# mulato-32m.net
KiCad netlist of a schematic drawn in EAGLE
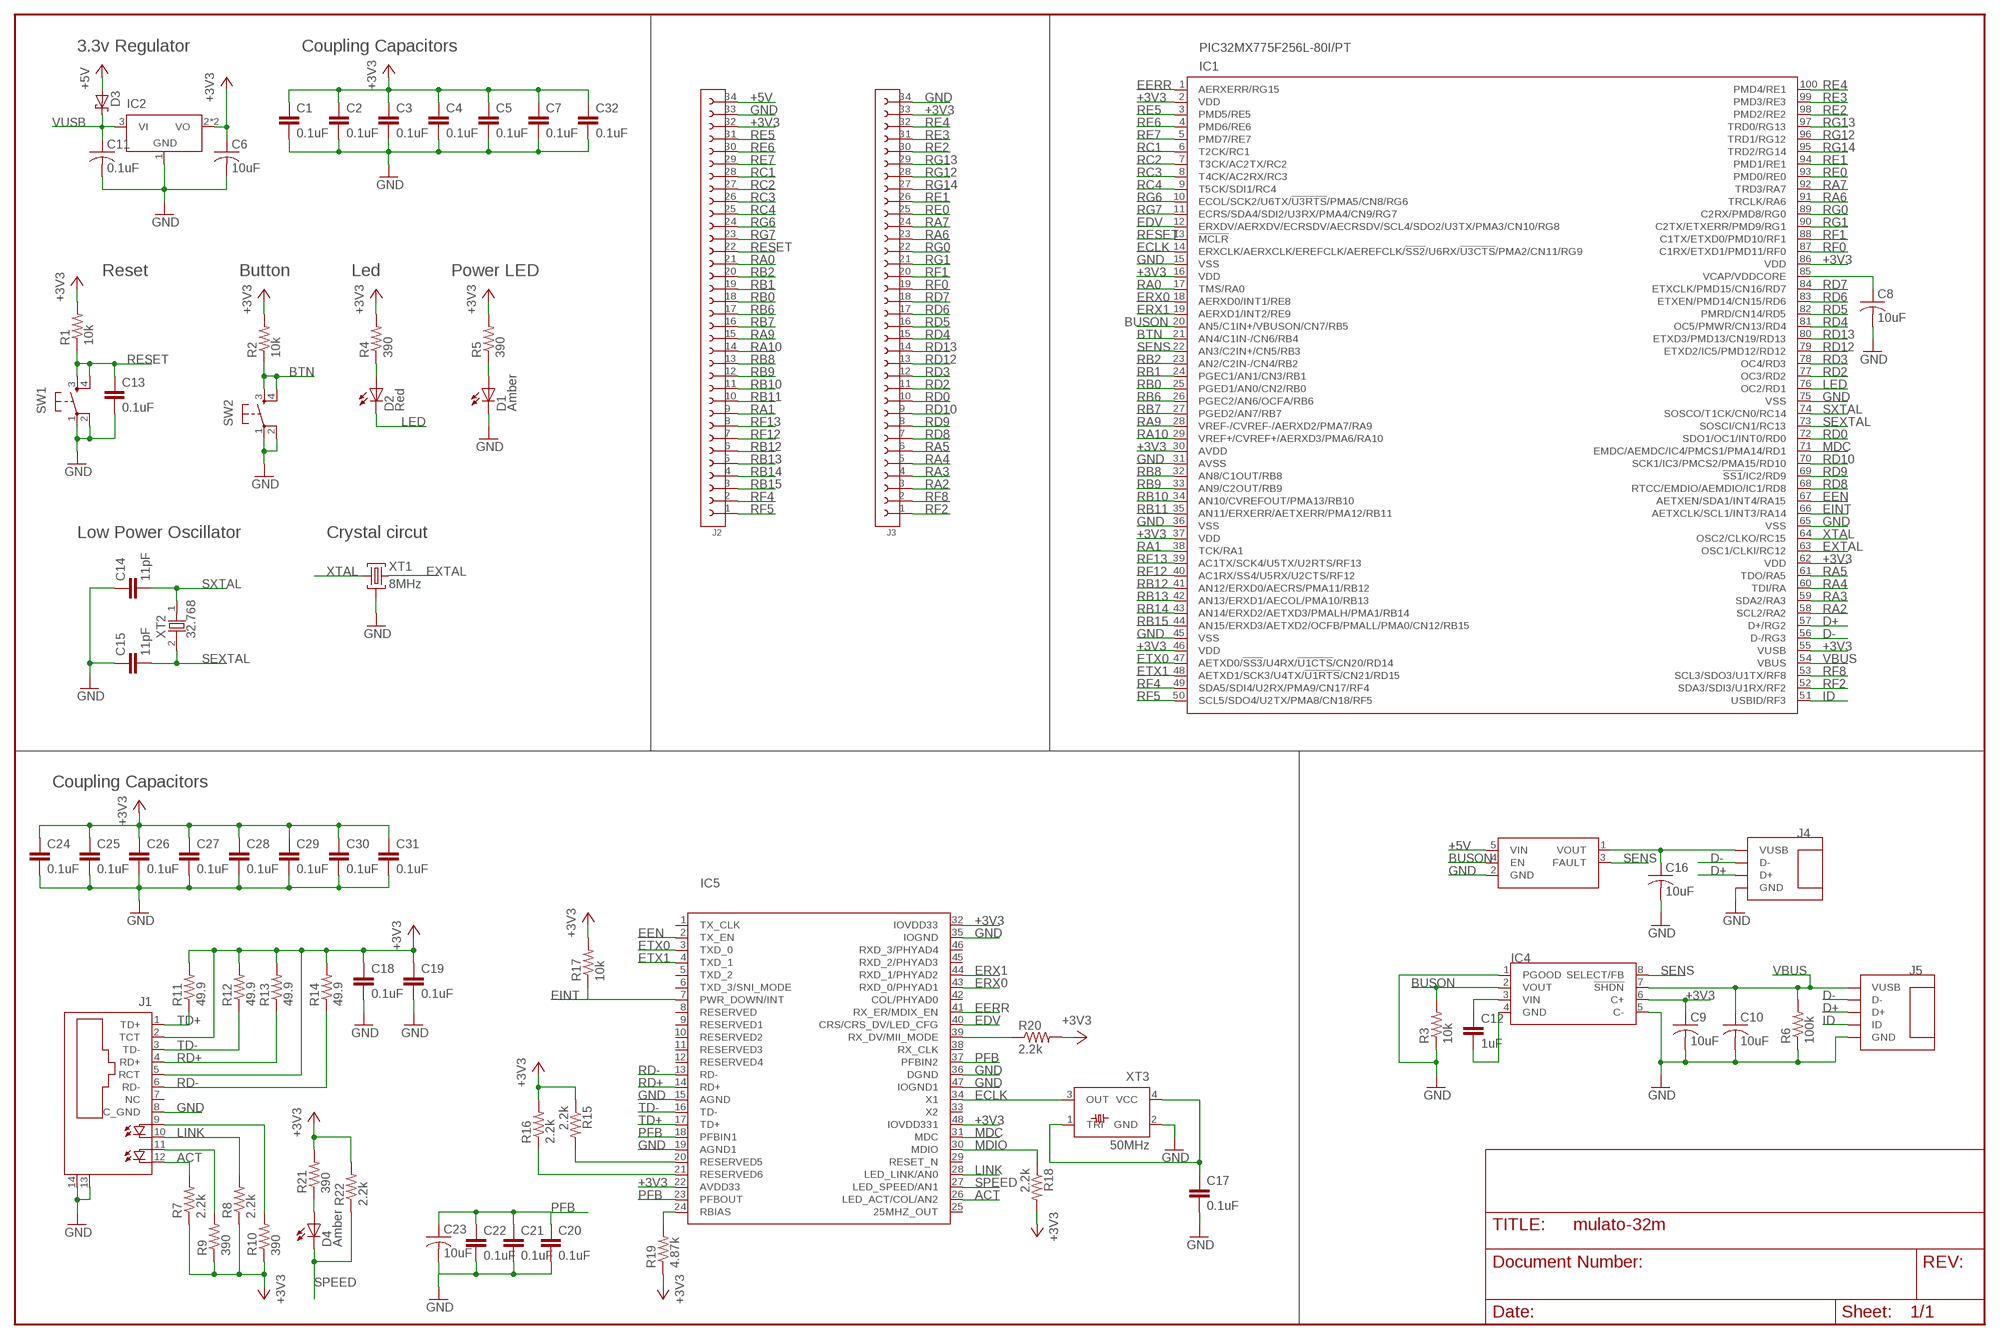
[diagram p0: schematic, sheet 1]

(export (version "E")
  (design (tool "Eeschema 10.0.6"))
  (components
    (comp (ref "C1")
      (value "0.1uF")
      (footprint "eagle-import:CAPC0603")
      (fields (field (name "MANUFACTURER") "KEMET"))
      (libsource (lib "eagle-import") (part "C?CVAC0603104Z3"))
    )
    (comp (ref "C2")
      (value "0.1uF")
      (footprint "eagle-import:CAPC0603")
      (fields (field (name "MANUFACTURER") "KEMET"))
      (libsource (lib "eagle-import") (part "C?CVAC0603104Z3"))
    )
    (comp (ref "C3")
      (value "0.1uF")
      (footprint "eagle-import:CAPC0603")
      (fields (field (name "MANUFACTURER") "KEMET"))
      (libsource (lib "eagle-import") (part "C?CVAC0603104Z3"))
    )
    (comp (ref "C4")
      (value "0.1uF")
      (footprint "eagle-import:CAPC0603")
      (fields (field (name "MANUFACTURER") "KEMET"))
      (libsource (lib "eagle-import") (part "C?CVAC0603104Z3"))
    )
    (comp (ref "C5")
      (value "0.1uF")
      (footprint "eagle-import:CAPC0603")
      (fields (field (name "MANUFACTURER") "KEMET"))
      (libsource (lib "eagle-import") (part "C?CVAC0603104Z3"))
    )
    (comp (ref "C6")
      (value "10uF")
      (footprint "eagle-import:CAPMP3216-18")
      (fields (field (name "MANUFACTURER") "KEMET"))
      (libsource (lib "eagle-import") (part "T491?A106K016AT"))
    )
    (comp (ref "C7")
      (value "0.1uF")
      (footprint "eagle-import:CAPC0603")
      (fields (field (name "MANUFACTURER") "KEMET"))
      (libsource (lib "eagle-import") (part "C?CVAC0603104Z3"))
    )
    (comp (ref "C8")
      (value "10uF")
      (footprint "eagle-import:CAPMP3216-18")
      (fields (field (name "MANUFACTURER") "KEMET"))
      (libsource (lib "eagle-import") (part "T491?A106K016AT"))
    )
    (comp (ref "C9")
      (value "10uF")
      (footprint "eagle-import:CAPMP3216-18")
      (fields (field (name "MANUFACTURER") "KEMET"))
      (libsource (lib "eagle-import") (part "T491?A106K016AT"))
    )
    (comp (ref "C10")
      (value "10uF")
      (footprint "eagle-import:CAPMP3216-18")
      (fields (field (name "MANUFACTURER") "KEMET"))
      (libsource (lib "eagle-import") (part "T491?A106K016AT"))
    )
    (comp (ref "C11")
      (value "0.1uF")
      (footprint "eagle-import:CAPMP3216-18")
      (fields (field (name "MANUFACTURER") "KEMET"))
      (libsource (lib "eagle-import") (part "T491?A104K050AT"))
    )
    (comp (ref "C12")
      (value "1uF")
      (footprint "eagle-import:CAPC0805")
      (fields (field (name "EAGLEUP") "CAPC0805"))
      (libsource (lib "eagle-import") (part "C?CRAC0805105K4"))
    )
    (comp (ref "C13")
      (value "0.1uF")
      (footprint "eagle-import:CAPC0603")
      (fields (field (name "MANUFACTURER") "KEMET"))
      (libsource (lib "eagle-import") (part "C?CVAC0603104Z3"))
    )
    (comp (ref "C14")
      (value "11pF")
      (footprint "eagle-import:CAPC0603")
      (fields (field (name "MANUFACTURER") "KEMET"))
      (libsource (lib "eagle-import") (part "C?CGAC0603110J5"))
    )
    (comp (ref "C15")
      (value "11pF")
      (footprint "eagle-import:CAPC0603")
      (fields (field (name "MANUFACTURER") "KEMET"))
      (libsource (lib "eagle-import") (part "C?CGAC0603110J5"))
    )
    (comp (ref "C16")
      (value "10uF")
      (footprint "eagle-import:CAPMP3216-18")
      (description "Capacitores de tantalio - SMD sólido 16volt 10uF 10% Lead Free")
      (fields
        (field (name "MANUFACTURER") "KEMET")
        (field (name "AVRG-PRICE") "0.18")
        (field (name "DIGIKEY") "399-8269-2-ND")
        (field (name "EAGLEUP") "CAPMP3216-18")
        (field (name "MANUFACTURER_1") "KEMET")
        (field (name "MOUSER") "80-T491A106K016")
        (field (name "OCTOPART-LINK") "http://octopart.com/t491a106k016at-kemet-145880")
      )
      (libsource (lib "eagle-import") (part "T491?A106K016AT"))
    )
    (comp (ref "C17")
      (value "0.1uF")
      (footprint "eagle-import:CAPC0603")
      (fields (field (name "MANUFACTURER") "KEMET"))
      (libsource (lib "eagle-import") (part "C?CVAC0603104Z3"))
    )
    (comp (ref "C18")
      (value "0.1uF")
      (footprint "eagle-import:CAPC0603")
      (fields (field (name "MANUFACTURER") "KEMET"))
      (libsource (lib "eagle-import") (part "C?CVAC0603104Z3"))
    )
    (comp (ref "C19")
      (value "0.1uF")
      (footprint "eagle-import:CAPC0603")
      (fields (field (name "MANUFACTURER") "KEMET"))
      (libsource (lib "eagle-import") (part "C?CVAC0603104Z3"))
    )
    (comp (ref "C20")
      (value "0.1uF")
      (footprint "eagle-import:CAPC0603")
      (fields (field (name "MANUFACTURER") "KEMET"))
      (libsource (lib "eagle-import") (part "C?CVAC0603104Z3"))
    )
    (comp (ref "C21")
      (value "0.1uF")
      (footprint "eagle-import:CAPC0603")
      (fields (field (name "MANUFACTURER") "KEMET"))
      (libsource (lib "eagle-import") (part "C?CVAC0603104Z3"))
    )
    (comp (ref "C22")
      (value "0.1uF")
      (footprint "eagle-import:CAPC0603")
      (fields (field (name "MANUFACTURER") "KEMET"))
      (libsource (lib "eagle-import") (part "C?CVAC0603104Z3"))
    )
    (comp (ref "C23")
      (value "10uF")
      (footprint "eagle-import:CAPMP3216-18")
      (fields (field (name "MANUFACTURER") "KEMET"))
      (libsource (lib "eagle-import") (part "T491?A106K016AT"))
    )
    (comp (ref "C24")
      (value "0.1uF")
      (footprint "eagle-import:CAPC0603")
      (fields (field (name "MANUFACTURER") "KEMET"))
      (libsource (lib "eagle-import") (part "C?CVAC0603104Z3"))
    )
    (comp (ref "C25")
      (value "0.1uF")
      (footprint "eagle-import:CAPC0603")
      (fields (field (name "MANUFACTURER") "KEMET"))
      (libsource (lib "eagle-import") (part "C?CVAC0603104Z3"))
    )
    (comp (ref "C26")
      (value "0.1uF")
      (footprint "eagle-import:CAPC0603")
      (fields (field (name "MANUFACTURER") "KEMET"))
      (libsource (lib "eagle-import") (part "C?CVAC0603104Z3"))
    )
    (comp (ref "C27")
      (value "0.1uF")
      (footprint "eagle-import:CAPC0603")
      (fields (field (name "MANUFACTURER") "KEMET"))
      (libsource (lib "eagle-import") (part "C?CVAC0603104Z3"))
    )
    (comp (ref "C28")
      (value "0.1uF")
      (footprint "eagle-import:CAPC0603")
      (fields (field (name "MANUFACTURER") "KEMET"))
      (libsource (lib "eagle-import") (part "C?CVAC0603104Z3"))
    )
    (comp (ref "C29")
      (value "0.1uF")
      (footprint "eagle-import:CAPC0603")
      (fields (field (name "MANUFACTURER") "KEMET"))
      (libsource (lib "eagle-import") (part "C?CVAC0603104Z3"))
    )
    (comp (ref "C30")
      (value "0.1uF")
      (footprint "eagle-import:CAPC0603")
      (fields (field (name "MANUFACTURER") "KEMET"))
      (libsource (lib "eagle-import") (part "C?CVAC0603104Z3"))
    )
    (comp (ref "C31")
      (value "0.1uF")
      (footprint "eagle-import:CAPC0603")
      (fields (field (name "MANUFACTURER") "KEMET"))
      (libsource (lib "eagle-import") (part "C?CVAC0603104Z3"))
    )
    (comp (ref "C32")
      (value "0.1uF")
      (footprint "eagle-import:CAPC0603")
      (fields (field (name "MANUFACTURER") "KEMET"))
      (libsource (lib "eagle-import") (part "C?CVAC0603104Z3"))
    )
    (comp (ref "D1")
      (value "Amber")
      (footprint "eagle-import:D0805")
      (libsource (lib "eagle-import") (part "SM0805AC"))
    )
    (comp (ref "D2")
      (value "Red")
      (footprint "eagle-import:D0805")
      (libsource (lib "eagle-import") (part "SM0805HC"))
    )
    (comp (ref "D3")
      (value "MBR0530T1G")
      (footprint "eagle-import:SOT123160X270-2N")
      (fields (field (name "EAGLEUP") "SOD123"))
      (libsource (lib "eagle-import") (part "MBR0530TG1"))
    )
    (comp (ref "D4")
      (value "Amber")
      (footprint "eagle-import:D0805")
      (libsource (lib "eagle-import") (part "SM0805AC"))
    )
    (comp (ref "IC1")
      (value "PIC32MX775F256L-80I/PT")
      (footprint "eagle-import:QFP40P1400X1400X100-100N")
      (libsource (lib "eagle-import") (part "PIC32MX7L?-80I/PT75F256"))
    )
    (comp (ref "IC2")
      (value "LD1117S33TR")
      (footprint "eagle-import:SOT230P700X180-4N")
      (fields (field (name "MANUFACTURER") "ST"))
      (libsource (lib "eagle-import") (part "LD1117?S33TR"))
    )
    (comp (ref "IC3")
      (value "SMTPS2141STR")
      (footprint "eagle-import:SOT95P280X100-5M")
      (fields (field (name "EAGLEUP") "SOT95P280X100-5N"))
      (libsource (lib "eagle-import") (part "SMTPS21?TRS41"))
    )
    (comp (ref "IC4")
      (value "MCP1253-33X50I/MS")
      (footprint "eagle-import:SOP65P490X109-8M")
      (fields (field (name "MANUFACTURER") "MICROCHIP"))
      (libsource (lib "eagle-import") (part "MCP125?I/MS3-33X50"))
    )
    (comp (ref "IC5")
      (value "DP83848C")
      (footprint "eagle-import:QFP50P900X900X160-48M")
      (libsource (lib "eagle-import") (part "DP83848C"))
    )
    (comp (ref "J1")
      (value "6605425-1")
      (footprint "eagle-import:RJ45-8N-2LEDS")
      (fields (field (name "MANUFACTURER") "TE"))
      (libsource (lib "eagle-import") (part "6605425-1"))
    )
    (comp (ref "J2")
      (value "61303411121")
      (footprint "eagle-import:PHSP254P8636X254X1154-34S")
      (libsource (lib "eagle-import") (part "6130341?1121"))
    )
    (comp (ref "J3")
      (value "61303411121")
      (footprint "eagle-import:PHSP254P8636X254X1154-34S")
      (libsource (lib "eagle-import") (part "6130341?1121"))
    )
    (comp (ref "J4")
      (value "292303-1")
      (footprint "eagle-import:USB-A")
      (libsource (lib "eagle-import") (part "292303-?1"))
    )
    (comp (ref "J5")
      (value "1981584-1")
      (footprint "eagle-import:USB-MICRO-B")
      (libsource (lib "eagle-import") (part "1981584-1"))
    )
    (comp (ref "R1")
      (value "10k")
      (footprint "eagle-import:RESC0603")
      (libsource (lib "eagle-import") (part "CRG?0603F10K10"))
    )
    (comp (ref "R2")
      (value "10k")
      (footprint "eagle-import:RESC0603")
      (libsource (lib "eagle-import") (part "CRG?0603F10K10"))
    )
    (comp (ref "R3")
      (value "10k")
      (footprint "eagle-import:RESC0603")
      (libsource (lib "eagle-import") (part "CRG?0603F10K10"))
    )
    (comp (ref "R4")
      (value "390")
      (footprint "eagle-import:RESC0603")
      (libsource (lib "eagle-import") (part "CRG?0603F390R"))
    )
    (comp (ref "R5")
      (value "390")
      (footprint "eagle-import:RESC0603")
      (libsource (lib "eagle-import") (part "CRG?0603F390R"))
    )
    (comp (ref "R6")
      (value "100k")
      (footprint "eagle-import:RESC0603")
      (libsource (lib "eagle-import") (part "CRG?0603F100K"))
    )
    (comp (ref "R7")
      (value "2.2k")
      (footprint "eagle-import:RESC0603")
      (libsource (lib "eagle-import") (part "CRG?0603F2K2"))
    )
    (comp (ref "R8")
      (value "2.2k")
      (footprint "eagle-import:RESC0603")
      (libsource (lib "eagle-import") (part "CRG?0603F2K2"))
    )
    (comp (ref "R9")
      (value "390")
      (footprint "eagle-import:RESC0603")
      (libsource (lib "eagle-import") (part "CRG?0603F390R"))
    )
    (comp (ref "R10")
      (value "390")
      (footprint "eagle-import:RESC0603")
      (libsource (lib "eagle-import") (part "CRG?0603F390R"))
    )
    (comp (ref "R11")
      (value "49.9")
      (footprint "eagle-import:RESC0603")
      (libsource (lib "eagle-import") (part "CRG?0603F49R9"))
    )
    (comp (ref "R12")
      (value "49.9")
      (footprint "eagle-import:RESC0603")
      (libsource (lib "eagle-import") (part "CRG?0603F49R9"))
    )
    (comp (ref "R13")
      (value "49.9")
      (footprint "eagle-import:RESC0603")
      (libsource (lib "eagle-import") (part "CRG?0603F49R9"))
    )
    (comp (ref "R14")
      (value "49.9")
      (footprint "eagle-import:RESC0603")
      (libsource (lib "eagle-import") (part "CRG?0603F49R9"))
    )
    (comp (ref "R15")
      (value "2.2k")
      (footprint "eagle-import:RESC0603")
      (libsource (lib "eagle-import") (part "CRG?0603F2K2"))
    )
    (comp (ref "R16")
      (value "2.2k")
      (footprint "eagle-import:RESC0603")
      (libsource (lib "eagle-import") (part "CRG?0603F2K2"))
    )
    (comp (ref "R17")
      (value "10k")
      (footprint "eagle-import:RESC0603")
      (libsource (lib "eagle-import") (part "CRG?0603F10K10"))
    )
    (comp (ref "R18")
      (value "2.2k")
      (footprint "eagle-import:RESC0603")
      (libsource (lib "eagle-import") (part "CRG?0603F2K2"))
    )
    (comp (ref "R19")
      (value "4.87k")
      (footprint "eagle-import:RESC0603")
      (libsource (lib "eagle-import") (part "CRG?0603F4K87"))
    )
    (comp (ref "R20")
      (value "2.2k")
      (footprint "eagle-import:RESC0603")
      (libsource (lib "eagle-import") (part "CRG?0603F2K2"))
    )
    (comp (ref "R21")
      (value "390")
      (footprint "eagle-import:RESC0603")
      (libsource (lib "eagle-import") (part "CRG?0603F390R"))
    )
    (comp (ref "R22")
      (value "2.2k")
      (footprint "eagle-import:RESC0603")
      (libsource (lib "eagle-import") (part "CRG?0603F2K2"))
    )
    (comp (ref "SW1")
      (value "TL3301NF160QJ")
      (footprint "eagle-import:TACT600X600-4J")
      (fields (field (name "MANUFACTURER") "E-SWITCH"))
      (libsource (lib "eagle-import") (part "TL3301?JNF160Q"))
    )
    (comp (ref "SW2")
      (value "TL3301NF160QJ")
      (footprint "eagle-import:TACT600X600-4J")
      (fields (field (name "MANUFACTURER") "E-SWITCH"))
      (libsource (lib "eagle-import") (part "TL3301?JNF160Q"))
    )
    (comp (ref "XT1")
      (value "8MHz")
      (footprint "eagle-import:CERAMIC740X340-3N")
      (fields (field (name "MANUFACTURER") "ABRACON"))
      (libsource (lib "eagle-import") (part "AWSCR-MGD-C8.00"))
    )
    (comp (ref "XT2")
      (value "32.768")
      (footprint "eagle-import:CEMIC320X150-2N")
      (fields (field (name "MANUFACTURER") "ABRACON"))
      (libsource (lib "eagle-import") (part "ABS07-120-32.768KHZ-T"))
    )
    (comp (ref "XT3")
      (value "50MHz")
      (footprint "eagle-import:CEMIC320X250-4N")
      (fields (field (name "MANUFACTURER") "ABRACON"))
      (libsource (lib "eagle-import") (part "ASE'-50.000MHZ-ET"))
    )
  )
  (nets
    (net (code "1") (name "+3V3") (class "Default")
      (node (ref "C1") (pin "1") (pinfunction "1_1") (pintype "passive"))
      (node (ref "C18") (pin "1") (pinfunction "1_1") (pintype "passive"))
      (node (ref "C19") (pin "1") (pinfunction "1_1") (pintype "passive"))
      (node (ref "C2") (pin "1") (pinfunction "1_1") (pintype "passive"))
      (node (ref "C24") (pin "1") (pinfunction "1_1") (pintype "passive"))
      (node (ref "C25") (pin "1") (pinfunction "1_1") (pintype "passive"))
      (node (ref "C26") (pin "1") (pinfunction "1_1") (pintype "passive"))
      (node (ref "C27") (pin "1") (pinfunction "1_1") (pintype "passive"))
      (node (ref "C28") (pin "1") (pinfunction "1_1") (pintype "passive"))
      (node (ref "C29") (pin "1") (pinfunction "1_1") (pintype "passive"))
      (node (ref "C3") (pin "1") (pinfunction "1_1") (pintype "passive"))
      (node (ref "C30") (pin "1") (pinfunction "1_1") (pintype "passive"))
      (node (ref "C31") (pin "1") (pinfunction "1_1") (pintype "passive"))
      (node (ref "C32") (pin "1") (pinfunction "1_1") (pintype "passive"))
      (node (ref "C4") (pin "1") (pinfunction "1_1") (pintype "passive"))
      (node (ref "C5") (pin "1") (pinfunction "1_1") (pintype "passive"))
      (node (ref "C6") (pin "1") (pinfunction "1_1") (pintype "passive"))
      (node (ref "C7") (pin "1") (pinfunction "1_1") (pintype "passive"))
      (node (ref "C9") (pin "1") (pinfunction "1_1") (pintype "passive"))
      (node (ref "IC1") (pin "16") (pinfunction "VDD_16") (pintype "power_in"))
      (node (ref "IC1") (pin "2") (pinfunction "VDD_2") (pintype "power_in"))
      (node (ref "IC1") (pin "30") (pinfunction "AVDD_30") (pintype "power_in"))
      (node (ref "IC1") (pin "37") (pinfunction "VDD_37") (pintype "power_in"))
      (node (ref "IC1") (pin "46") (pinfunction "VDD_46") (pintype "power_in"))
      (node (ref "IC1") (pin "55") (pinfunction "VUSB_55") (pintype "power_in"))
      (node (ref "IC1") (pin "62") (pinfunction "VDD_62") (pintype "power_in"))
      (node (ref "IC1") (pin "86") (pinfunction "VDD_86") (pintype "power_in"))
      (node (ref "IC2") (pin "2") (pinfunction "VO_2") (pintype "input"))
      (node (ref "IC2") (pin "4") (pinfunction "VO_4") (pintype "input"))
      (node (ref "IC4") (pin "6") (pinfunction "C+_6") (pintype "bidirectional"))
      (node (ref "IC5") (pin "22") (pinfunction "AVDD33_22") (pintype "bidirectional"))
      (node (ref "IC5") (pin "32") (pinfunction "IOVDD33_32") (pintype "power_in"))
      (node (ref "IC5") (pin "48") (pinfunction "IOVDD331_48") (pintype "power_in"))
      (node (ref "J1") (pin "2") (pinfunction "TCT_2") (pintype "passive"))
      (node (ref "J1") (pin "5") (pinfunction "RCT_5") (pintype "passive"))
      (node (ref "J2") (pin "32") (pinfunction "32_32") (pintype "passive"))
      (node (ref "J3") (pin "33") (pinfunction "33_33") (pintype "passive"))
      (node (ref "R1") (pin "P$2") (pinfunction "2_P$2") (pintype "passive"))
      (node (ref "R10") (pin "P$1") (pinfunction "1_P$1") (pintype "passive"))
      (node (ref "R11") (pin "P$2") (pinfunction "2_P$2") (pintype "passive"))
      (node (ref "R12") (pin "P$2") (pinfunction "2_P$2") (pintype "passive"))
      (node (ref "R13") (pin "P$2") (pinfunction "2_P$2") (pintype "passive"))
      (node (ref "R14") (pin "P$2") (pinfunction "2_P$2") (pintype "passive"))
      (node (ref "R15") (pin "P$1") (pinfunction "1_P$1") (pintype "passive"))
      (node (ref "R16") (pin "P$2") (pinfunction "2_P$2") (pintype "passive"))
      (node (ref "R17") (pin "P$2") (pinfunction "2_P$2") (pintype "passive"))
      (node (ref "R18") (pin "P$2") (pinfunction "2_P$2") (pintype "passive"))
      (node (ref "R19") (pin "P$1") (pinfunction "1_P$1") (pintype "passive"))
      (node (ref "R2") (pin "P$2") (pinfunction "2_P$2") (pintype "passive"))
      (node (ref "R20") (pin "P$2") (pinfunction "2_P$2") (pintype "passive"))
      (node (ref "R21") (pin "P$2") (pinfunction "2_P$2") (pintype "passive"))
      (node (ref "R22") (pin "P$2") (pinfunction "2_P$2") (pintype "passive"))
      (node (ref "R4") (pin "P$2") (pinfunction "2_P$2") (pintype "passive"))
      (node (ref "R5") (pin "P$2") (pinfunction "2_P$2") (pintype "passive"))
      (node (ref "R7") (pin "P$1") (pinfunction "1_P$1") (pintype "passive"))
      (node (ref "R8") (pin "P$1") (pinfunction "1_P$1") (pintype "passive"))
      (node (ref "R9") (pin "P$1") (pinfunction "1_P$1") (pintype "passive"))
    )
    (net (code "2") (name "+5V") (class "Default")
      (node (ref "D3") (pin "1") (pinfunction "A_1") (pintype "passive"))
      (node (ref "IC3") (pin "5") (pinfunction "VIN_5") (pintype "power_in"))
      (node (ref "J2") (pin "34") (pinfunction "34_34") (pintype "passive"))
    )
    (net (code "3") (name "/ACT") (class "Default")
      (node (ref "IC5") (pin "26") (pinfunction "LED_ACT/COL/AN2_26") (pintype "bidirectional"))
      (node (ref "J1") (pin "12") (pinfunction "C1_12") (pintype "passive"))
      (node (ref "R7") (pin "P$2") (pinfunction "2_P$2") (pintype "passive"))
    )
    (net (code "4") (name "/BTN") (class "Default")
      (node (ref "IC1") (pin "21") (pinfunction "AN4/C1IN-/CN6/RB4_21") (pintype "bidirectional"))
      (node (ref "R2") (pin "P$1") (pinfunction "1_P$1") (pintype "passive"))
      (node (ref "SW2") (pin "3") (pinfunction "S_3") (pintype "passive"))
      (node (ref "SW2") (pin "4") (pinfunction "S1_4") (pintype "passive"))
    )
    (net (code "5") (name "/BUSON") (class "Default")
      (node (ref "IC1") (pin "20") (pinfunction "AN5/C1IN+/VBUSON/CN7/RB5_20") (pintype "bidirectional"))
      (node (ref "IC3") (pin "4") (pinfunction "EN_4") (pintype "bidirectional"))
      (node (ref "IC4") (pin "2") (pinfunction "VOUT_2") (pintype "bidirectional"))
      (node (ref "R3") (pin "P$2") (pinfunction "2_P$2") (pintype "passive"))
    )
    (net (code "6") (name "/D+") (class "Default")
      (node (ref "IC1") (pin "57") (pinfunction "D+/RG2_57") (pintype "bidirectional"))
      (node (ref "J4") (pin "2") (pinfunction "D+_2") (pintype "bidirectional"))
      (node (ref "J5") (pin "3") (pinfunction "D+_3") (pintype "bidirectional"))
    )
    (net (code "7") (name "/D-") (class "Default")
      (node (ref "IC1") (pin "56") (pinfunction "D-/RG3_56") (pintype "bidirectional"))
      (node (ref "J4") (pin "3") (pinfunction "D-_3") (pintype "bidirectional"))
      (node (ref "J5") (pin "2") (pinfunction "D-_2") (pintype "bidirectional"))
    )
    (net (code "8") (name "/ECLK") (class "Default")
      (node (ref "IC1") (pin "14") (pinfunction "ERXCLK/AERXCLK/EREFCLK/AEREFCLK/~{SS2}/U6RX/~{U3CTS}/PMA2/CN11/RG9_14") (pintype "bidirectional"))
      (node (ref "IC5") (pin "34") (pinfunction "X1_34") (pintype "bidirectional"))
      (node (ref "XT3") (pin "3") (pinfunction "OUT_3") (pintype "output"))
    )
    (net (code "9") (name "/EDV") (class "Default")
      (node (ref "IC1") (pin "12") (pinfunction "ERXDV/AERXDV/ECRSDV/AECRSDV/SCL4/SDO2/U3TX/PMA3/CN10/RG8_12") (pintype "bidirectional"))
      (node (ref "IC5") (pin "40") (pinfunction "CRS/CRS_DV/LED_CFG_40") (pintype "bidirectional"))
    )
    (net (code "10") (name "/EEN") (class "Default")
      (node (ref "IC1") (pin "67") (pinfunction "AETXEN/SDA1/INT4/RA15_67") (pintype "bidirectional"))
      (node (ref "IC5") (pin "2") (pinfunction "TX_EN_2") (pintype "bidirectional"))
    )
    (net (code "11") (name "/EERR") (class "Default")
      (node (ref "IC1") (pin "1") (pinfunction "AERXERR/RG15_1") (pintype "bidirectional"))
      (node (ref "IC5") (pin "41") (pinfunction "RX_ER/MDIX_EN_41") (pintype "bidirectional"))
    )
    (net (code "12") (name "/EINT") (class "Default")
      (node (ref "IC1") (pin "66") (pinfunction "AETXCLK/SCL1/INT3/RA14_66") (pintype "bidirectional"))
      (node (ref "IC5") (pin "7") (pinfunction "PWR_DOWN/INT_7") (pintype "bidirectional"))
      (node (ref "R17") (pin "P$1") (pinfunction "1_P$1") (pintype "passive"))
    )
    (net (code "13") (name "/ERX0") (class "Default")
      (node (ref "IC1") (pin "18") (pinfunction "AERXD0/INT1/RE8_18") (pintype "bidirectional"))
      (node (ref "IC5") (pin "43") (pinfunction "RXD_0/PHYAD1_43") (pintype "bidirectional"))
    )
    (net (code "14") (name "/ERX1") (class "Default")
      (node (ref "IC1") (pin "19") (pinfunction "AERXD1/INT2/RE9_19") (pintype "bidirectional"))
      (node (ref "IC5") (pin "44") (pinfunction "RXD_1/PHYAD2_44") (pintype "bidirectional"))
    )
    (net (code "15") (name "/ETX0") (class "Default")
      (node (ref "IC1") (pin "47") (pinfunction "AETXD0/~{SS3}/U4RX/~{U1CTS}/CN20/RD14_47") (pintype "bidirectional"))
      (node (ref "IC5") (pin "3") (pinfunction "TXD_0_3") (pintype "bidirectional"))
    )
    (net (code "16") (name "/ETX1") (class "Default")
      (node (ref "IC1") (pin "48") (pinfunction "AETXD1/SCK3/U4TX/~{U1RTS}/CN21/RD15_48") (pintype "bidirectional"))
      (node (ref "IC5") (pin "4") (pinfunction "TXD_1_4") (pintype "bidirectional"))
    )
    (net (code "17") (name "/EXTAL") (class "Default")
      (node (ref "IC1") (pin "63") (pinfunction "OSC1/CLKI/RC12_63") (pintype "bidirectional"))
      (node (ref "XT1") (pin "3") (pinfunction "3_3") (pintype "passive"))
    )
    (net (code "18") (name "/ID") (class "Default")
      (node (ref "IC1") (pin "51") (pinfunction "USBID/RF3_51") (pintype "bidirectional"))
      (node (ref "J5") (pin "4") (pinfunction "ID_4") (pintype "bidirectional"))
    )
    (net (code "19") (name "/LED") (class "Default")
      (node (ref "D2") (pin "2") (pinfunction "C_2") (pintype "passive"))
      (node (ref "IC1") (pin "76") (pinfunction "OC2/RD1_76") (pintype "bidirectional"))
    )
    (net (code "20") (name "/LINK") (class "Default")
      (node (ref "IC5") (pin "28") (pinfunction "LED_LINK/AN0_28") (pintype "bidirectional"))
      (node (ref "J1") (pin "10") (pinfunction "C_10") (pintype "passive"))
      (node (ref "R8") (pin "P$2") (pinfunction "2_P$2") (pintype "passive"))
    )
    (net (code "21") (name "/MDC") (class "Default")
      (node (ref "IC1") (pin "71") (pinfunction "EMDC/AEMDC/IC4/PMCS1/PMA14/RD1_71") (pintype "bidirectional"))
      (node (ref "IC5") (pin "31") (pinfunction "MDC_31") (pintype "bidirectional"))
    )
    (net (code "22") (name "/MDIO") (class "Default")
      (node (ref "IC5") (pin "30") (pinfunction "MDIO_30") (pintype "bidirectional"))
      (node (ref "R18") (pin "P$1") (pinfunction "1_P$1") (pintype "passive"))
    )
    (net (code "23") (name "/PFB") (class "Default")
      (node (ref "C20") (pin "1") (pinfunction "1_1") (pintype "passive"))
      (node (ref "C21") (pin "1") (pinfunction "1_1") (pintype "passive"))
      (node (ref "C22") (pin "1") (pinfunction "1_1") (pintype "passive"))
      (node (ref "C23") (pin "1") (pinfunction "1_1") (pintype "passive"))
      (node (ref "IC5") (pin "18") (pinfunction "PFBIN1_18") (pintype "bidirectional"))
      (node (ref "IC5") (pin "23") (pinfunction "PFBOUT_23") (pintype "bidirectional"))
      (node (ref "IC5") (pin "37") (pinfunction "PFBIN2_37") (pintype "bidirectional"))
    )
    (net (code "24") (name "/RA0") (class "Default")
      (node (ref "IC1") (pin "17") (pinfunction "TMS/RA0_17") (pintype "bidirectional"))
      (node (ref "J2") (pin "21") (pinfunction "21_21") (pintype "passive"))
    )
    (net (code "25") (name "/RA1") (class "Default")
      (node (ref "IC1") (pin "38") (pinfunction "TCK/RA1_38") (pintype "bidirectional"))
      (node (ref "J2") (pin "9") (pinfunction "9_9") (pintype "passive"))
    )
    (net (code "26") (name "/RA2") (class "Default")
      (node (ref "IC1") (pin "58") (pinfunction "SCL2/RA2_58") (pintype "bidirectional"))
      (node (ref "J3") (pin "3") (pinfunction "3_3") (pintype "passive"))
    )
    (net (code "27") (name "/RA3") (class "Default")
      (node (ref "IC1") (pin "59") (pinfunction "SDA2/RA3_59") (pintype "bidirectional"))
      (node (ref "J3") (pin "4") (pinfunction "4_4") (pintype "passive"))
    )
    (net (code "28") (name "/RA4") (class "Default")
      (node (ref "IC1") (pin "60") (pinfunction "TDI/RA_60") (pintype "bidirectional"))
      (node (ref "J3") (pin "5") (pinfunction "5_5") (pintype "passive"))
    )
    (net (code "29") (name "/RA5") (class "Default")
      (node (ref "IC1") (pin "61") (pinfunction "TDO/RA5_61") (pintype "bidirectional"))
      (node (ref "J3") (pin "6") (pinfunction "6_6") (pintype "passive"))
    )
    (net (code "30") (name "/RA6") (class "Default")
      (node (ref "IC1") (pin "91") (pinfunction "TRCLK/RA6_91") (pintype "bidirectional"))
      (node (ref "J3") (pin "23") (pinfunction "23_23") (pintype "passive"))
    )
    (net (code "31") (name "/RA7") (class "Default")
      (node (ref "IC1") (pin "92") (pinfunction "TRD3/RA7_92") (pintype "bidirectional"))
      (node (ref "J3") (pin "24") (pinfunction "24_24") (pintype "passive"))
    )
    (net (code "32") (name "/RA9") (class "Default")
      (node (ref "IC1") (pin "28") (pinfunction "VREF-/CVREF-/AERXD2/PMA7/RA9_28") (pintype "bidirectional"))
      (node (ref "J2") (pin "15") (pinfunction "15_15") (pintype "passive"))
    )
    (net (code "33") (name "/RA10") (class "Default")
      (node (ref "IC1") (pin "29") (pinfunction "VREF+/CVREF+/AERXD3/PMA6/RA10_29") (pintype "bidirectional"))
      (node (ref "J2") (pin "14") (pinfunction "14_14") (pintype "passive"))
    )
    (net (code "34") (name "/RB0") (class "Default")
      (node (ref "IC1") (pin "25") (pinfunction "PGED1/AN0/CN2/RB0_25") (pintype "bidirectional"))
      (node (ref "J2") (pin "18") (pinfunction "18_18") (pintype "passive"))
    )
    (net (code "35") (name "/RB1") (class "Default")
      (node (ref "IC1") (pin "24") (pinfunction "PGEC1/AN1/CN3/RB1_24") (pintype "bidirectional"))
      (node (ref "J2") (pin "19") (pinfunction "19_19") (pintype "passive"))
    )
    (net (code "36") (name "/RB2") (class "Default")
      (node (ref "IC1") (pin "23") (pinfunction "AN2/C2IN-/CN4/RB2_23") (pintype "bidirectional"))
      (node (ref "J2") (pin "20") (pinfunction "20_20") (pintype "passive"))
    )
    (net (code "37") (name "/RB6") (class "Default")
      (node (ref "IC1") (pin "26") (pinfunction "PGEC2/AN6/OCFA/RB6_26") (pintype "bidirectional"))
      (node (ref "J2") (pin "17") (pinfunction "17_17") (pintype "passive"))
    )
    (net (code "38") (name "/RB7") (class "Default")
      (node (ref "IC1") (pin "27") (pinfunction "PGED2/AN7/RB7_27") (pintype "bidirectional"))
      (node (ref "J2") (pin "16") (pinfunction "16_16") (pintype "passive"))
    )
    (net (code "39") (name "/RB8") (class "Default")
      (node (ref "IC1") (pin "32") (pinfunction "AN8/C1OUT/RB8_32") (pintype "bidirectional"))
      (node (ref "J2") (pin "13") (pinfunction "13_13") (pintype "passive"))
    )
    (net (code "40") (name "/RB9") (class "Default")
      (node (ref "IC1") (pin "33") (pinfunction "AN9/C2OUT/RB9_33") (pintype "bidirectional"))
      (node (ref "J2") (pin "12") (pinfunction "12_12") (pintype "passive"))
    )
    (net (code "41") (name "/RB10") (class "Default")
      (node (ref "IC1") (pin "34") (pinfunction "AN10/CVREFOUT/PMA13/RB10_34") (pintype "bidirectional"))
      (node (ref "J2") (pin "11") (pinfunction "11_11") (pintype "passive"))
    )
    (net (code "42") (name "/RB11") (class "Default")
      (node (ref "IC1") (pin "35") (pinfunction "AN11/ERXERR/AETXERR/PMA12/RB11_35") (pintype "bidirectional"))
      (node (ref "J2") (pin "10") (pinfunction "10_10") (pintype "passive"))
    )
    (net (code "43") (name "/RB12") (class "Default")
      (node (ref "IC1") (pin "41") (pinfunction "AN12/ERXD0/AECRS/PMA11/RB12_41") (pintype "bidirectional"))
      (node (ref "J2") (pin "6") (pinfunction "6_6") (pintype "passive"))
    )
    (net (code "44") (name "/RB13") (class "Default")
      (node (ref "IC1") (pin "42") (pinfunction "AN13/ERXD1/AECOL/PMA10/RB13_42") (pintype "bidirectional"))
      (node (ref "J2") (pin "5") (pinfunction "5_5") (pintype "passive"))
    )
    (net (code "45") (name "/RB14") (class "Default")
      (node (ref "IC1") (pin "43") (pinfunction "AN14/ERXD2/AETXD3/PMALH/PMA1/RB14_43") (pintype "bidirectional"))
      (node (ref "J2") (pin "4") (pinfunction "4_4") (pintype "passive"))
    )
    (net (code "46") (name "/RB15") (class "Default")
      (node (ref "IC1") (pin "44") (pinfunction "AN15/ERXD3/AETXD2/OCFB/PMALL/PMA0/CN12/RB15_44") (pintype "bidirectional"))
      (node (ref "J2") (pin "3") (pinfunction "3_3") (pintype "passive"))
    )
    (net (code "47") (name "/RC1") (class "Default")
      (node (ref "IC1") (pin "6") (pinfunction "T2CK/RC1_6") (pintype "bidirectional"))
      (node (ref "J2") (pin "28") (pinfunction "28_28") (pintype "passive"))
    )
    (net (code "48") (name "/RC2") (class "Default")
      (node (ref "IC1") (pin "7") (pinfunction "T3CK/AC2TX/RC2_7") (pintype "bidirectional"))
      (node (ref "J2") (pin "27") (pinfunction "27_27") (pintype "passive"))
    )
    (net (code "49") (name "/RC3") (class "Default")
      (node (ref "IC1") (pin "8") (pinfunction "T4CK/AC2RX/RC3_8") (pintype "bidirectional"))
      (node (ref "J2") (pin "26") (pinfunction "26_26") (pintype "passive"))
    )
    (net (code "50") (name "/RC4") (class "Default")
      (node (ref "IC1") (pin "9") (pinfunction "T5CK/SDI1/RC4_9") (pintype "bidirectional"))
      (node (ref "J2") (pin "25") (pinfunction "25_25") (pintype "passive"))
    )
    (net (code "51") (name "/RD+") (class "Default")
      (node (ref "IC5") (pin "14") (pinfunction "RD+_14") (pintype "bidirectional"))
      (node (ref "J1") (pin "4") (pinfunction "RD+_4") (pintype "passive"))
      (node (ref "R13") (pin "P$1") (pinfunction "1_P$1") (pintype "passive"))
    )
    (net (code "52") (name "/RD-") (class "Default")
      (node (ref "IC5") (pin "13") (pinfunction "RD-_13") (pintype "bidirectional"))
      (node (ref "J1") (pin "6") (pinfunction "RD-_6") (pintype "passive"))
      (node (ref "R14") (pin "P$1") (pinfunction "1_P$1") (pintype "passive"))
    )
    (net (code "53") (name "/RD0") (class "Default")
      (node (ref "IC1") (pin "72") (pinfunction "SDO1/OC1/INT0/RD0_72") (pintype "bidirectional"))
      (node (ref "J3") (pin "10") (pinfunction "10_10") (pintype "passive"))
    )
    (net (code "54") (name "/RD2") (class "Default")
      (node (ref "IC1") (pin "77") (pinfunction "OC3/RD2_77") (pintype "bidirectional"))
      (node (ref "J3") (pin "11") (pinfunction "11_11") (pintype "passive"))
    )
    (net (code "55") (name "/RD3") (class "Default")
      (node (ref "IC1") (pin "78") (pinfunction "OC4/RD3_78") (pintype "bidirectional"))
      (node (ref "J3") (pin "12") (pinfunction "12_12") (pintype "passive"))
    )
    (net (code "56") (name "/RD4") (class "Default")
      (node (ref "IC1") (pin "81") (pinfunction "OC5/PMWR/CN13/RD4_81") (pintype "bidirectional"))
      (node (ref "J3") (pin "15") (pinfunction "15_15") (pintype "passive"))
    )
    (net (code "57") (name "/RD5") (class "Default")
      (node (ref "IC1") (pin "82") (pinfunction "PMRD/CN14/RD5_82") (pintype "bidirectional"))
      (node (ref "J3") (pin "16") (pinfunction "16_16") (pintype "passive"))
    )
    (net (code "58") (name "/RD6") (class "Default")
      (node (ref "IC1") (pin "83") (pinfunction "ETXEN/PMD14/CN15/RD6_83") (pintype "bidirectional"))
      (node (ref "J3") (pin "17") (pinfunction "17_17") (pintype "passive"))
    )
    (net (code "59") (name "/RD7") (class "Default")
      (node (ref "IC1") (pin "84") (pinfunction "ETXCLK/PMD15/CN16/RD7_84") (pintype "bidirectional"))
      (node (ref "J3") (pin "18") (pinfunction "18_18") (pintype "passive"))
    )
    (net (code "60") (name "/RD8") (class "Default")
      (node (ref "IC1") (pin "68") (pinfunction "RTCC/EMDIO/AEMDIO/IC1/RD8_68") (pintype "bidirectional"))
      (node (ref "J3") (pin "7") (pinfunction "7_7") (pintype "passive"))
    )
    (net (code "61") (name "/RD9") (class "Default")
      (node (ref "IC1") (pin "69") (pinfunction "~{SS1}/IC2/RD9_69") (pintype "bidirectional"))
      (node (ref "J3") (pin "8") (pinfunction "8_8") (pintype "passive"))
    )
    (net (code "62") (name "/RD10") (class "Default")
      (node (ref "IC1") (pin "70") (pinfunction "SCK1/IC3/PMCS2/PMA15/RD10_70") (pintype "bidirectional"))
      (node (ref "J3") (pin "9") (pinfunction "9_9") (pintype "passive"))
    )
    (net (code "63") (name "/RD12") (class "Default")
      (node (ref "IC1") (pin "79") (pinfunction "ETXD2/IC5/PMD12/RD12_79") (pintype "bidirectional"))
      (node (ref "J3") (pin "13") (pinfunction "13_13") (pintype "passive"))
    )
    (net (code "64") (name "/RD13") (class "Default")
      (node (ref "IC1") (pin "80") (pinfunction "ETXD3/PMD13/CN19/RD13_80") (pintype "bidirectional"))
      (node (ref "J3") (pin "14") (pinfunction "14_14") (pintype "passive"))
    )
    (net (code "65") (name "/RE0") (class "Default")
      (node (ref "IC1") (pin "93") (pinfunction "PMD0/RE0_93") (pintype "bidirectional"))
      (node (ref "J3") (pin "25") (pinfunction "25_25") (pintype "passive"))
    )
    (net (code "66") (name "/RE1") (class "Default")
      (node (ref "IC1") (pin "94") (pinfunction "PMD1/RE1_94") (pintype "bidirectional"))
      (node (ref "J3") (pin "26") (pinfunction "26_26") (pintype "passive"))
    )
    (net (code "67") (name "/RE2") (class "Default")
      (node (ref "IC1") (pin "98") (pinfunction "PMD2/RE2_98") (pintype "bidirectional"))
      (node (ref "J3") (pin "30") (pinfunction "30_30") (pintype "passive"))
    )
    (net (code "68") (name "/RE3") (class "Default")
      (node (ref "IC1") (pin "99") (pinfunction "PMD3/RE3_99") (pintype "bidirectional"))
      (node (ref "J3") (pin "31") (pinfunction "31_31") (pintype "passive"))
    )
    (net (code "69") (name "/RE4") (class "Default")
      (node (ref "IC1") (pin "100") (pinfunction "PMD4/RE1_100") (pintype "bidirectional"))
      (node (ref "J3") (pin "32") (pinfunction "32_32") (pintype "passive"))
    )
    (net (code "70") (name "/RE5") (class "Default")
      (node (ref "IC1") (pin "3") (pinfunction "PMD5/RE5_3") (pintype "bidirectional"))
      (node (ref "J2") (pin "31") (pinfunction "31_31") (pintype "passive"))
    )
    (net (code "71") (name "/RE6") (class "Default")
      (node (ref "IC1") (pin "4") (pinfunction "PMD6/RE6_4") (pintype "bidirectional"))
      (node (ref "J2") (pin "30") (pinfunction "30_30") (pintype "passive"))
    )
    (net (code "72") (name "/RE7") (class "Default")
      (node (ref "IC1") (pin "5") (pinfunction "PMD7/RE7_5") (pintype "bidirectional"))
      (node (ref "J2") (pin "29") (pinfunction "29_29") (pintype "passive"))
    )
    (net (code "73") (name "/RESET") (class "Default")
      (node (ref "C13") (pin "1") (pinfunction "1_1") (pintype "passive"))
      (node (ref "IC1") (pin "13") (pinfunction "~{MCLR}_13") (pintype "bidirectional"))
      (node (ref "J2") (pin "22") (pinfunction "22_22") (pintype "passive"))
      (node (ref "R1") (pin "P$1") (pinfunction "1_P$1") (pintype "passive"))
      (node (ref "SW1") (pin "3") (pinfunction "S_3") (pintype "passive"))
      (node (ref "SW1") (pin "4") (pinfunction "S1_4") (pintype "passive"))
    )
    (net (code "74") (name "/RF0") (class "Default")
      (node (ref "IC1") (pin "87") (pinfunction "C1RX/ETXD1/PMD11/RF0_87") (pintype "bidirectional"))
      (node (ref "J3") (pin "19") (pinfunction "19_19") (pintype "passive"))
    )
    (net (code "75") (name "/RF1") (class "Default")
      (node (ref "IC1") (pin "88") (pinfunction "C1TX/ETXD0/PMD10/RF1_88") (pintype "bidirectional"))
      (node (ref "J3") (pin "20") (pinfunction "20_20") (pintype "passive"))
    )
    (net (code "76") (name "/RF2") (class "Default")
      (node (ref "IC1") (pin "52") (pinfunction "SDA3/SDI3/U1RX/RF2_52") (pintype "bidirectional"))
      (node (ref "J3") (pin "1") (pinfunction "1_1") (pintype "passive"))
    )
    (net (code "77") (name "/RF4") (class "Default")
      (node (ref "IC1") (pin "49") (pinfunction "SDA5/SDI4/U2RX/PMA9/CN17/RF4_49") (pintype "bidirectional"))
      (node (ref "J2") (pin "2") (pinfunction "2_2") (pintype "passive"))
    )
    (net (code "78") (name "/RF5") (class "Default")
      (node (ref "IC1") (pin "50") (pinfunction "SCL5/SDO4/U2TX/PMA8/CN18/RF5_50") (pintype "bidirectional"))
      (node (ref "J2") (pin "1") (pinfunction "1_1") (pintype "passive"))
    )
    (net (code "79") (name "/RF8") (class "Default")
      (node (ref "IC1") (pin "53") (pinfunction "SCL3/SDO3/U1TX/RF8_53") (pintype "bidirectional"))
      (node (ref "J3") (pin "2") (pinfunction "2_2") (pintype "passive"))
    )
    (net (code "80") (name "/RF12") (class "Default")
      (node (ref "IC1") (pin "40") (pinfunction "AC1RX/SS4/U5RX/U2CTS/RF12_40") (pintype "bidirectional"))
      (node (ref "J2") (pin "7") (pinfunction "7_7") (pintype "passive"))
    )
    (net (code "81") (name "/RF13") (class "Default")
      (node (ref "IC1") (pin "39") (pinfunction "AC1TX/SCK4/U5TX/U2RTS/RF13_39") (pintype "bidirectional"))
      (node (ref "J2") (pin "8") (pinfunction "8_8") (pintype "passive"))
    )
    (net (code "82") (name "/RG0") (class "Default")
      (node (ref "IC1") (pin "89") (pinfunction "C2RX/PMD8/RG0_89") (pintype "bidirectional"))
      (node (ref "J3") (pin "22") (pinfunction "22_22") (pintype "passive"))
    )
    (net (code "83") (name "/RG1") (class "Default")
      (node (ref "IC1") (pin "90") (pinfunction "C2TX/ETXERR/PMD9/RG1_90") (pintype "bidirectional"))
      (node (ref "J3") (pin "21") (pinfunction "21_21") (pintype "passive"))
    )
    (net (code "84") (name "/RG6") (class "Default")
      (node (ref "IC1") (pin "10") (pinfunction "ECOL/SCK2/U6TX/~{U3RTS}/PMA5/CN8/RG6_10") (pintype "bidirectional"))
      (node (ref "J2") (pin "24") (pinfunction "24_24") (pintype "passive"))
    )
    (net (code "85") (name "/RG7") (class "Default")
      (node (ref "IC1") (pin "11") (pinfunction "ECRS/SDA4/SDI2/U3RX/PMA4/CN9/RG7_11") (pintype "bidirectional"))
      (node (ref "J2") (pin "23") (pinfunction "23_23") (pintype "passive"))
    )
    (net (code "86") (name "/RG12") (class "Default")
      (node (ref "IC1") (pin "96") (pinfunction "TRD1/RG12_96") (pintype "bidirectional"))
      (node (ref "J3") (pin "28") (pinfunction "28_28") (pintype "passive"))
    )
    (net (code "87") (name "/RG13") (class "Default")
      (node (ref "IC1") (pin "97") (pinfunction "TRD0/RG13_97") (pintype "bidirectional"))
      (node (ref "J3") (pin "29") (pinfunction "29_29") (pintype "passive"))
    )
    (net (code "88") (name "/RG14") (class "Default")
      (node (ref "IC1") (pin "95") (pinfunction "TRD2/RG14_95") (pintype "bidirectional"))
      (node (ref "J3") (pin "27") (pinfunction "27_27") (pintype "passive"))
    )
    (net (code "89") (name "/SENS") (class "Default")
      (node (ref "IC1") (pin "22") (pinfunction "AN3/C2IN+/CN5/RB3_22") (pintype "bidirectional"))
      (node (ref "IC3") (pin "3") (pinfunction "FAULT_3") (pintype "bidirectional"))
      (node (ref "IC4") (pin "8") (pinfunction "SELECT/FB_8") (pintype "bidirectional"))
    )
    (net (code "90") (name "/SEXTAL") (class "Default")
      (node (ref "C15") (pin "2") (pinfunction "2_2") (pintype "passive"))
      (node (ref "IC1") (pin "73") (pinfunction "SOSCI/CN1/RC13_73") (pintype "bidirectional"))
      (node (ref "XT2") (pin "2") (pinfunction "1_2") (pintype "passive"))
    )
    (net (code "91") (name "/SPEED") (class "Default")
      (node (ref "D4") (pin "2") (pinfunction "C_2") (pintype "passive"))
      (node (ref "IC5") (pin "27") (pinfunction "LED_SPEED/AN1_27") (pintype "bidirectional"))
      (node (ref "R22") (pin "P$1") (pinfunction "1_P$1") (pintype "passive"))
    )
    (net (code "92") (name "/SXTAL") (class "Default")
      (node (ref "C14") (pin "2") (pinfunction "2_2") (pintype "passive"))
      (node (ref "IC1") (pin "74") (pinfunction "SOSCO/T1CK/CN0/RC14_74") (pintype "bidirectional"))
      (node (ref "XT2") (pin "1") (pinfunction "2_1") (pintype "passive"))
    )
    (net (code "93") (name "/TD+") (class "Default")
      (node (ref "IC5") (pin "17") (pinfunction "TD+_17") (pintype "bidirectional"))
      (node (ref "J1") (pin "1") (pinfunction "TD+_1") (pintype "passive"))
      (node (ref "R11") (pin "P$1") (pinfunction "1_P$1") (pintype "passive"))
    )
    (net (code "94") (name "/TD-") (class "Default")
      (node (ref "IC5") (pin "16") (pinfunction "TD-_16") (pintype "bidirectional"))
      (node (ref "J1") (pin "3") (pinfunction "TD-_3") (pintype "passive"))
      (node (ref "R12") (pin "P$1") (pinfunction "1_P$1") (pintype "passive"))
    )
    (net (code "95") (name "/VBUS") (class "Default")
      (node (ref "C10") (pin "1") (pinfunction "1_1") (pintype "passive"))
      (node (ref "IC1") (pin "54") (pinfunction "VBUS_54") (pintype "power_in"))
      (node (ref "IC4") (pin "7") (pinfunction "~{SHDN}_7") (pintype "bidirectional"))
      (node (ref "J5") (pin "1") (pinfunction "VUSB_1") (pintype "bidirectional"))
      (node (ref "R6") (pin "P$2") (pinfunction "2_P$2") (pintype "passive"))
    )
    (net (code "96") (name "/VUSB") (class "Default")
      (node (ref "C11") (pin "1") (pinfunction "1_1") (pintype "passive"))
      (node (ref "D3") (pin "2") (pinfunction "C_2") (pintype "passive"))
      (node (ref "IC2") (pin "3") (pinfunction "VI_3") (pintype "input"))
    )
    (net (code "97") (name "/XTAL") (class "Default")
      (node (ref "IC1") (pin "64") (pinfunction "OSC2/CLKO/RC15_64") (pintype "bidirectional"))
      (node (ref "XT1") (pin "1") (pinfunction "1_1") (pintype "passive"))
    )
    (net (code "98") (name "GND") (class "Default")
      (node (ref "C1") (pin "2") (pinfunction "2_2") (pintype "passive"))
      (node (ref "C10") (pin "2") (pinfunction "2_2") (pintype "passive"))
      (node (ref "C11") (pin "2") (pinfunction "2_2") (pintype "passive"))
      (node (ref "C13") (pin "2") (pinfunction "2_2") (pintype "passive"))
      (node (ref "C14") (pin "1") (pinfunction "1_1") (pintype "passive"))
      (node (ref "C15") (pin "1") (pinfunction "1_1") (pintype "passive"))
      (node (ref "C16") (pin "2") (pinfunction "2_2") (pintype "passive"))
      (node (ref "C17") (pin "2") (pinfunction "2_2") (pintype "passive"))
      (node (ref "C18") (pin "2") (pinfunction "2_2") (pintype "passive"))
      (node (ref "C19") (pin "2") (pinfunction "2_2") (pintype "passive"))
      (node (ref "C2") (pin "2") (pinfunction "2_2") (pintype "passive"))
      (node (ref "C20") (pin "2") (pinfunction "2_2") (pintype "passive"))
      (node (ref "C21") (pin "2") (pinfunction "2_2") (pintype "passive"))
      (node (ref "C22") (pin "2") (pinfunction "2_2") (pintype "passive"))
      (node (ref "C23") (pin "2") (pinfunction "2_2") (pintype "passive"))
      (node (ref "C24") (pin "2") (pinfunction "2_2") (pintype "passive"))
      (node (ref "C25") (pin "2") (pinfunction "2_2") (pintype "passive"))
      (node (ref "C26") (pin "2") (pinfunction "2_2") (pintype "passive"))
      (node (ref "C27") (pin "2") (pinfunction "2_2") (pintype "passive"))
      (node (ref "C28") (pin "2") (pinfunction "2_2") (pintype "passive"))
      (node (ref "C29") (pin "2") (pinfunction "2_2") (pintype "passive"))
      (node (ref "C3") (pin "2") (pinfunction "2_2") (pintype "passive"))
      (node (ref "C30") (pin "2") (pinfunction "2_2") (pintype "passive"))
      (node (ref "C31") (pin "2") (pinfunction "2_2") (pintype "passive"))
      (node (ref "C32") (pin "2") (pinfunction "2_2") (pintype "passive"))
      (node (ref "C4") (pin "2") (pinfunction "2_2") (pintype "passive"))
      (node (ref "C5") (pin "2") (pinfunction "2_2") (pintype "passive"))
      (node (ref "C6") (pin "2") (pinfunction "2_2") (pintype "passive"))
      (node (ref "C7") (pin "2") (pinfunction "2_2") (pintype "passive"))
      (node (ref "C8") (pin "2") (pinfunction "2_2") (pintype "passive"))
      (node (ref "C9") (pin "2") (pinfunction "2_2") (pintype "passive"))
      (node (ref "D1") (pin "2") (pinfunction "C_2") (pintype "passive"))
      (node (ref "IC1") (pin "15") (pinfunction "VSS_15") (pintype "power_in"))
      (node (ref "IC1") (pin "31") (pinfunction "AVSS_31") (pintype "power_in"))
      (node (ref "IC1") (pin "36") (pinfunction "VSS_36") (pintype "power_in"))
      (node (ref "IC1") (pin "45") (pinfunction "VSS_45") (pintype "power_in"))
      (node (ref "IC1") (pin "65") (pinfunction "VSS_65") (pintype "power_in"))
      (node (ref "IC1") (pin "75") (pinfunction "VSS_75") (pintype "power_in"))
      (node (ref "IC2") (pin "1") (pinfunction "GND_1") (pintype "power_in"))
      (node (ref "IC3") (pin "2") (pinfunction "GND_2") (pintype "power_in"))
      (node (ref "IC4") (pin "1") (pinfunction "PGOOD_1") (pintype "bidirectional"))
      (node (ref "IC4") (pin "5") (pinfunction "C-_5") (pintype "bidirectional"))
      (node (ref "IC5") (pin "15") (pinfunction "AGND_15") (pintype "power_in"))
      (node (ref "IC5") (pin "19") (pinfunction "AGND1_19") (pintype "power_in"))
      (node (ref "IC5") (pin "35") (pinfunction "IOGND_35") (pintype "power_in"))
      (node (ref "IC5") (pin "36") (pinfunction "DGND_36") (pintype "power_in"))
      (node (ref "IC5") (pin "47") (pinfunction "IOGND1_47") (pintype "power_in"))
      (node (ref "J1") (pin "13") (pinfunction "CH1_13") (pintype "passive"))
      (node (ref "J1") (pin "14") (pinfunction "CH2_14") (pintype "passive"))
      (node (ref "J1") (pin "8") (pinfunction "C_GND_8") (pintype "passive"))
      (node (ref "J2") (pin "33") (pinfunction "33_33") (pintype "passive"))
      (node (ref "J3") (pin "34") (pinfunction "34_34") (pintype "passive"))
      (node (ref "J4") (pin "4") (pinfunction "GND_4") (pintype "bidirectional"))
      (node (ref "J5") (pin "5") (pinfunction "GND_5") (pintype "bidirectional"))
      (node (ref "R3") (pin "P$1") (pinfunction "1_P$1") (pintype "passive"))
      (node (ref "R6") (pin "P$1") (pinfunction "1_P$1") (pintype "passive"))
      (node (ref "SW1") (pin "1") (pinfunction "P_1") (pintype "passive"))
      (node (ref "SW1") (pin "2") (pinfunction "P1_2") (pintype "passive"))
      (node (ref "SW2") (pin "1") (pinfunction "P_1") (pintype "passive"))
      (node (ref "SW2") (pin "2") (pinfunction "P1_2") (pintype "passive"))
      (node (ref "XT1") (pin "2") (pinfunction "2_2") (pintype "passive"))
      (node (ref "XT3") (pin "2") (pinfunction "GND_2") (pintype "power_in"))
    )
    (net (code "99") (name "Net-(D1-A)") (class "Default")
      (node (ref "D1") (pin "1") (pinfunction "A_1") (pintype "passive"))
      (node (ref "R5") (pin "P$1") (pinfunction "1_P$1") (pintype "passive"))
    )
    (net (code "100") (name "Net-(D2-A)") (class "Default")
      (node (ref "D2") (pin "1") (pinfunction "A_1") (pintype "passive"))
      (node (ref "R4") (pin "P$1") (pinfunction "1_P$1") (pintype "passive"))
    )
    (net (code "101") (name "Net-(D4-A)") (class "Default")
      (node (ref "D4") (pin "1") (pinfunction "A_1") (pintype "passive"))
      (node (ref "R21") (pin "P$1") (pinfunction "1_P$1") (pintype "passive"))
    )
    (net (code "102") (name "Net-(IC1-VCAP{slash}VDDCORE)") (class "Default")
      (node (ref "C8") (pin "1") (pinfunction "1_1") (pintype "passive"))
      (node (ref "IC1") (pin "85") (pinfunction "VCAP/VDDCORE_85") (pintype "power_in"))
    )
    (net (code "103") (name "Net-(IC3-VOUT)") (class "Default")
      (node (ref "C16") (pin "1") (pinfunction "1_1") (pintype "passive"))
      (node (ref "IC3") (pin "1") (pinfunction "VOUT_1") (pintype "power_in"))
      (node (ref "J4") (pin "1") (pinfunction "VUSB_1") (pintype "bidirectional"))
    )
    (net (code "104") (name "Net-(IC4-GND)") (class "Default")
      (node (ref "C12") (pin "2") (pinfunction "2_2") (pintype "passive"))
      (node (ref "IC4") (pin "4") (pinfunction "GND_4") (pintype "bidirectional"))
    )
    (net (code "105") (name "Net-(IC4-VIN)") (class "Default")
      (node (ref "C12") (pin "1") (pinfunction "1_1") (pintype "passive"))
      (node (ref "IC4") (pin "3") (pinfunction "VIN_3") (pintype "bidirectional"))
    )
    (net (code "106") (name "Net-(IC5-RBIAS)") (class "Default")
      (node (ref "IC5") (pin "24") (pinfunction "RBIAS_24") (pintype "bidirectional"))
      (node (ref "R19") (pin "P$2") (pinfunction "2_P$2") (pintype "passive"))
    )
    (net (code "107") (name "Net-(IC5-RESERVED5)") (class "Default")
      (node (ref "IC5") (pin "20") (pinfunction "RESERVED5_20") (pintype "bidirectional"))
      (node (ref "R15") (pin "P$2") (pinfunction "2_P$2") (pintype "passive"))
    )
    (net (code "108") (name "Net-(IC5-RESERVED6)") (class "Default")
      (node (ref "IC5") (pin "21") (pinfunction "RESERVED6_21") (pintype "bidirectional"))
      (node (ref "R16") (pin "P$1") (pinfunction "1_P$1") (pintype "passive"))
    )
    (net (code "109") (name "Net-(IC5-RX_DV{slash}MII_MODE)") (class "Default")
      (node (ref "IC5") (pin "39") (pinfunction "RX_DV/MII_MODE_39") (pintype "bidirectional"))
      (node (ref "R20") (pin "P$1") (pinfunction "1_P$1") (pintype "passive"))
    )
    (net (code "110") (name "Net-(J1-A)") (class "Default")
      (node (ref "J1") (pin "9") (pinfunction "A_9") (pintype "passive"))
      (node (ref "R10") (pin "P$2") (pinfunction "2_P$2") (pintype "passive"))
    )
    (net (code "111") (name "Net-(J1-A1)") (class "Default")
      (node (ref "J1") (pin "11") (pinfunction "A1_11") (pintype "passive"))
      (node (ref "R9") (pin "P$2") (pinfunction "2_P$2") (pintype "passive"))
    )
    (net (code "112") (name "Net-(XT3-TRI)") (class "Default")
      (node (ref "C17") (pin "1") (pinfunction "1_1") (pintype "passive"))
      (node (ref "XT3") (pin "1") (pinfunction "TRI_1") (pintype "power_in"))
      (node (ref "XT3") (pin "4") (pinfunction "VCC_4") (pintype "power_in"))
    )
    (net (code "113") (name "unconnected-(IC5-25MHZ_OUT-Pad25)") (class "Default")
      (node (ref "IC5") (pin "25") (pinfunction "25MHZ_OUT_25") (pintype "bidirectional"))
    )
    (net (code "114") (name "unconnected-(IC5-COL{slash}PHYAD0-Pad42)") (class "Default")
      (node (ref "IC5") (pin "42") (pinfunction "COL/PHYAD0_42") (pintype "bidirectional"))
    )
    (net (code "115") (name "unconnected-(IC5-RESERVED-Pad8)") (class "Default")
      (node (ref "IC5") (pin "8") (pinfunction "RESERVED_8") (pintype "bidirectional"))
    )
    (net (code "116") (name "unconnected-(IC5-RESERVED1-Pad9)") (class "Default")
      (node (ref "IC5") (pin "9") (pinfunction "RESERVED1_9") (pintype "bidirectional"))
    )
    (net (code "117") (name "unconnected-(IC5-RESERVED2-Pad10)") (class "Default")
      (node (ref "IC5") (pin "10") (pinfunction "RESERVED2_10") (pintype "bidirectional"))
    )
    (net (code "118") (name "unconnected-(IC5-RESERVED3-Pad11)") (class "Default")
      (node (ref "IC5") (pin "11") (pinfunction "RESERVED3_11") (pintype "bidirectional"))
    )
    (net (code "119") (name "unconnected-(IC5-RESERVED4-Pad12)") (class "Default")
      (node (ref "IC5") (pin "12") (pinfunction "RESERVED4_12") (pintype "bidirectional"))
    )
    (net (code "120") (name "unconnected-(IC5-RESET_N-Pad29)") (class "Default")
      (node (ref "IC5") (pin "29") (pinfunction "RESET_N_29") (pintype "bidirectional"))
    )
    (net (code "121") (name "unconnected-(IC5-RXD_2{slash}PHYAD3-Pad45)") (class "Default")
      (node (ref "IC5") (pin "45") (pinfunction "RXD_2/PHYAD3_45") (pintype "bidirectional"))
    )
    (net (code "122") (name "unconnected-(IC5-RXD_3{slash}PHYAD4-Pad46)") (class "Default")
      (node (ref "IC5") (pin "46") (pinfunction "RXD_3/PHYAD4_46") (pintype "bidirectional"))
    )
    (net (code "123") (name "unconnected-(IC5-RX_CLK-Pad38)") (class "Default")
      (node (ref "IC5") (pin "38") (pinfunction "RX_CLK_38") (pintype "bidirectional"))
    )
    (net (code "124") (name "unconnected-(IC5-TXD_2-Pad5)") (class "Default")
      (node (ref "IC5") (pin "5") (pinfunction "TXD_2_5") (pintype "bidirectional"))
    )
    (net (code "125") (name "unconnected-(IC5-TXD_3{slash}SNI_MODE-Pad6)") (class "Default")
      (node (ref "IC5") (pin "6") (pinfunction "TXD_3/SNI_MODE_6") (pintype "bidirectional"))
    )
    (net (code "126") (name "unconnected-(IC5-TX_CLK-Pad1)") (class "Default")
      (node (ref "IC5") (pin "1") (pinfunction "TX_CLK_1") (pintype "bidirectional"))
    )
    (net (code "127") (name "unconnected-(IC5-X2-Pad33)") (class "Default")
      (node (ref "IC5") (pin "33") (pinfunction "X2_33") (pintype "bidirectional"))
    )
    (net (code "128") (name "unconnected-(J1-NC-Pad7)") (class "Default")
      (node (ref "J1") (pin "7") (pinfunction "NC_7") (pintype "passive"))
    )
  )
)
